# Logic.net
KiCad netlist of a schematic drawn in EAGLE
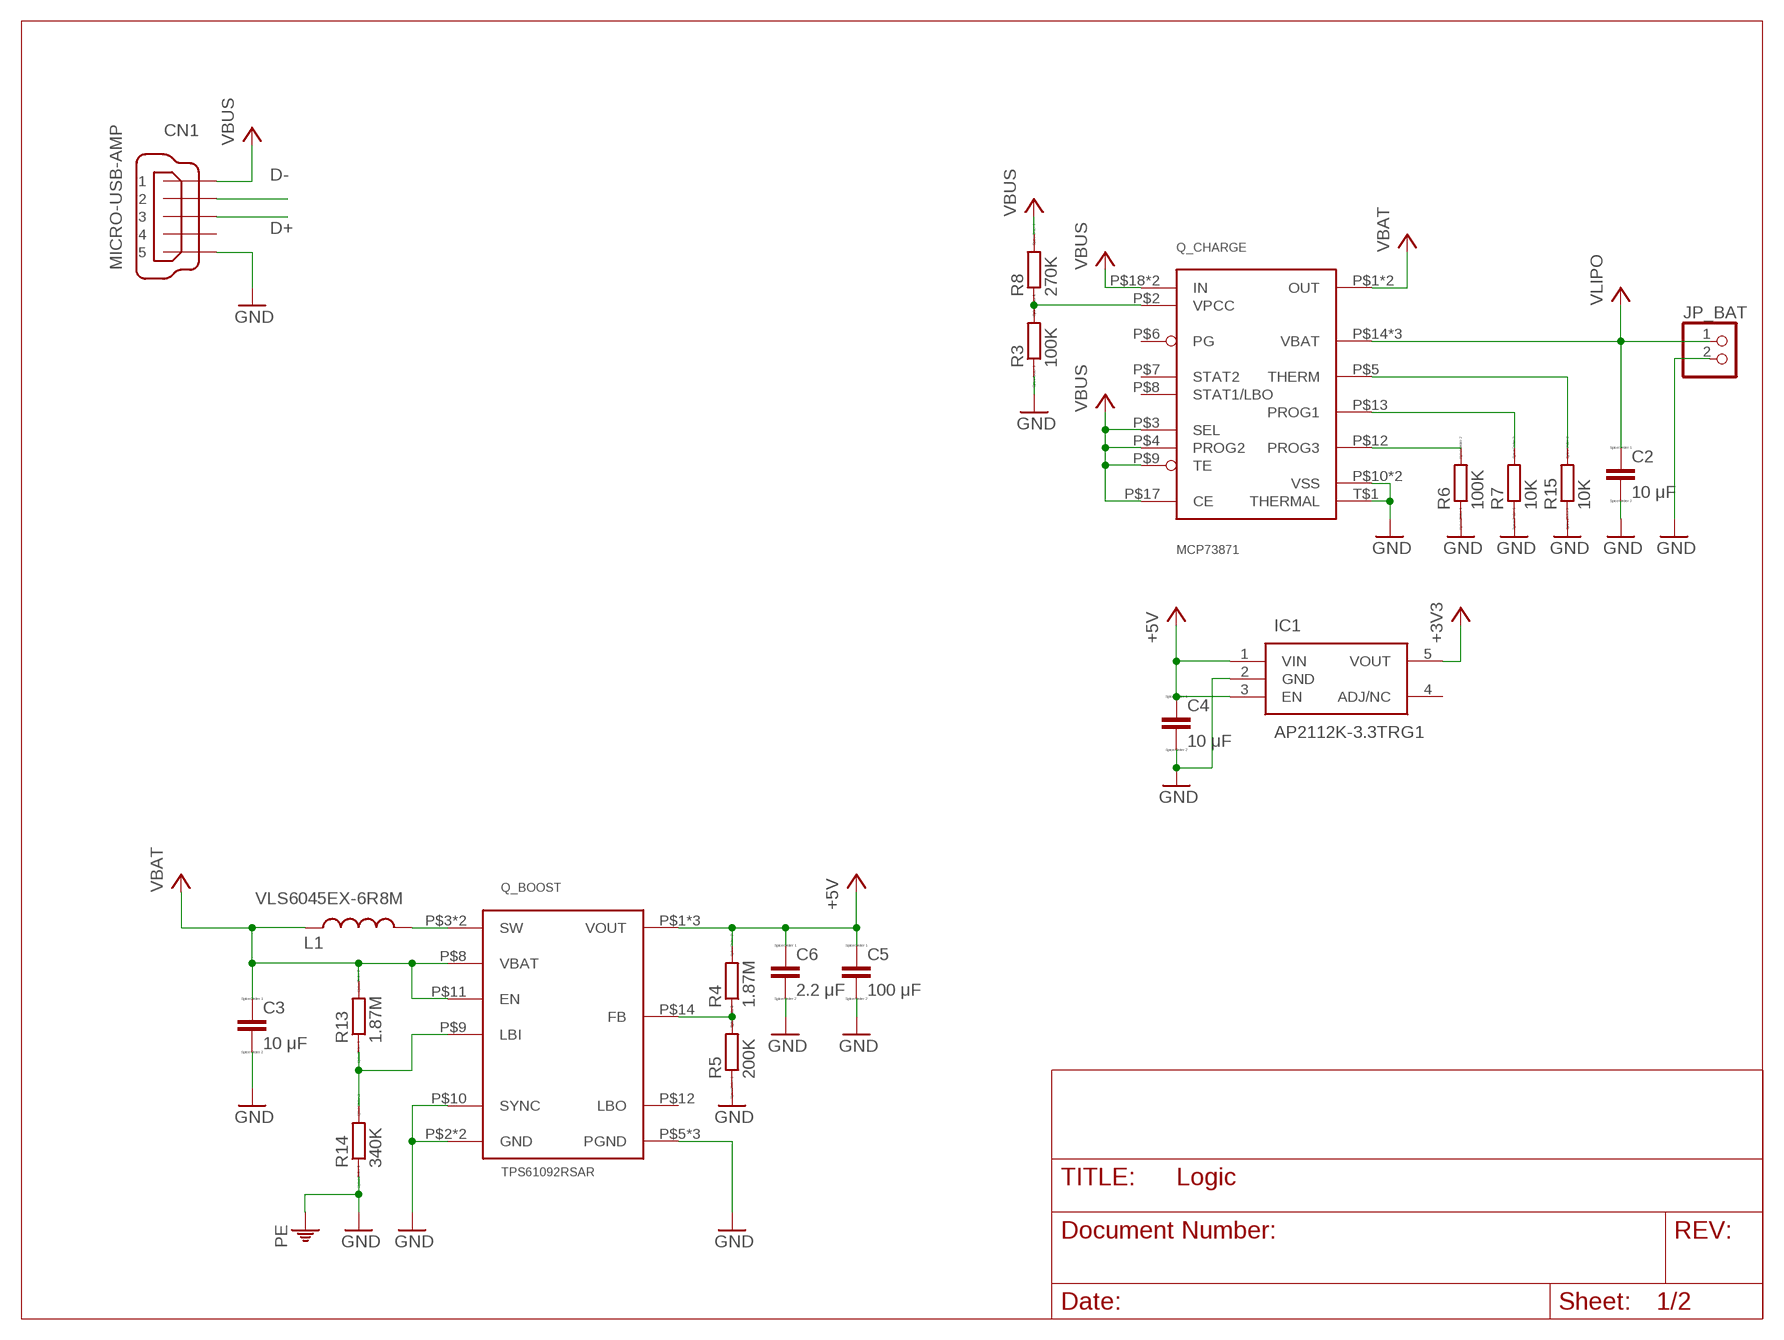
[diagram p0: schematic, sheet 1]
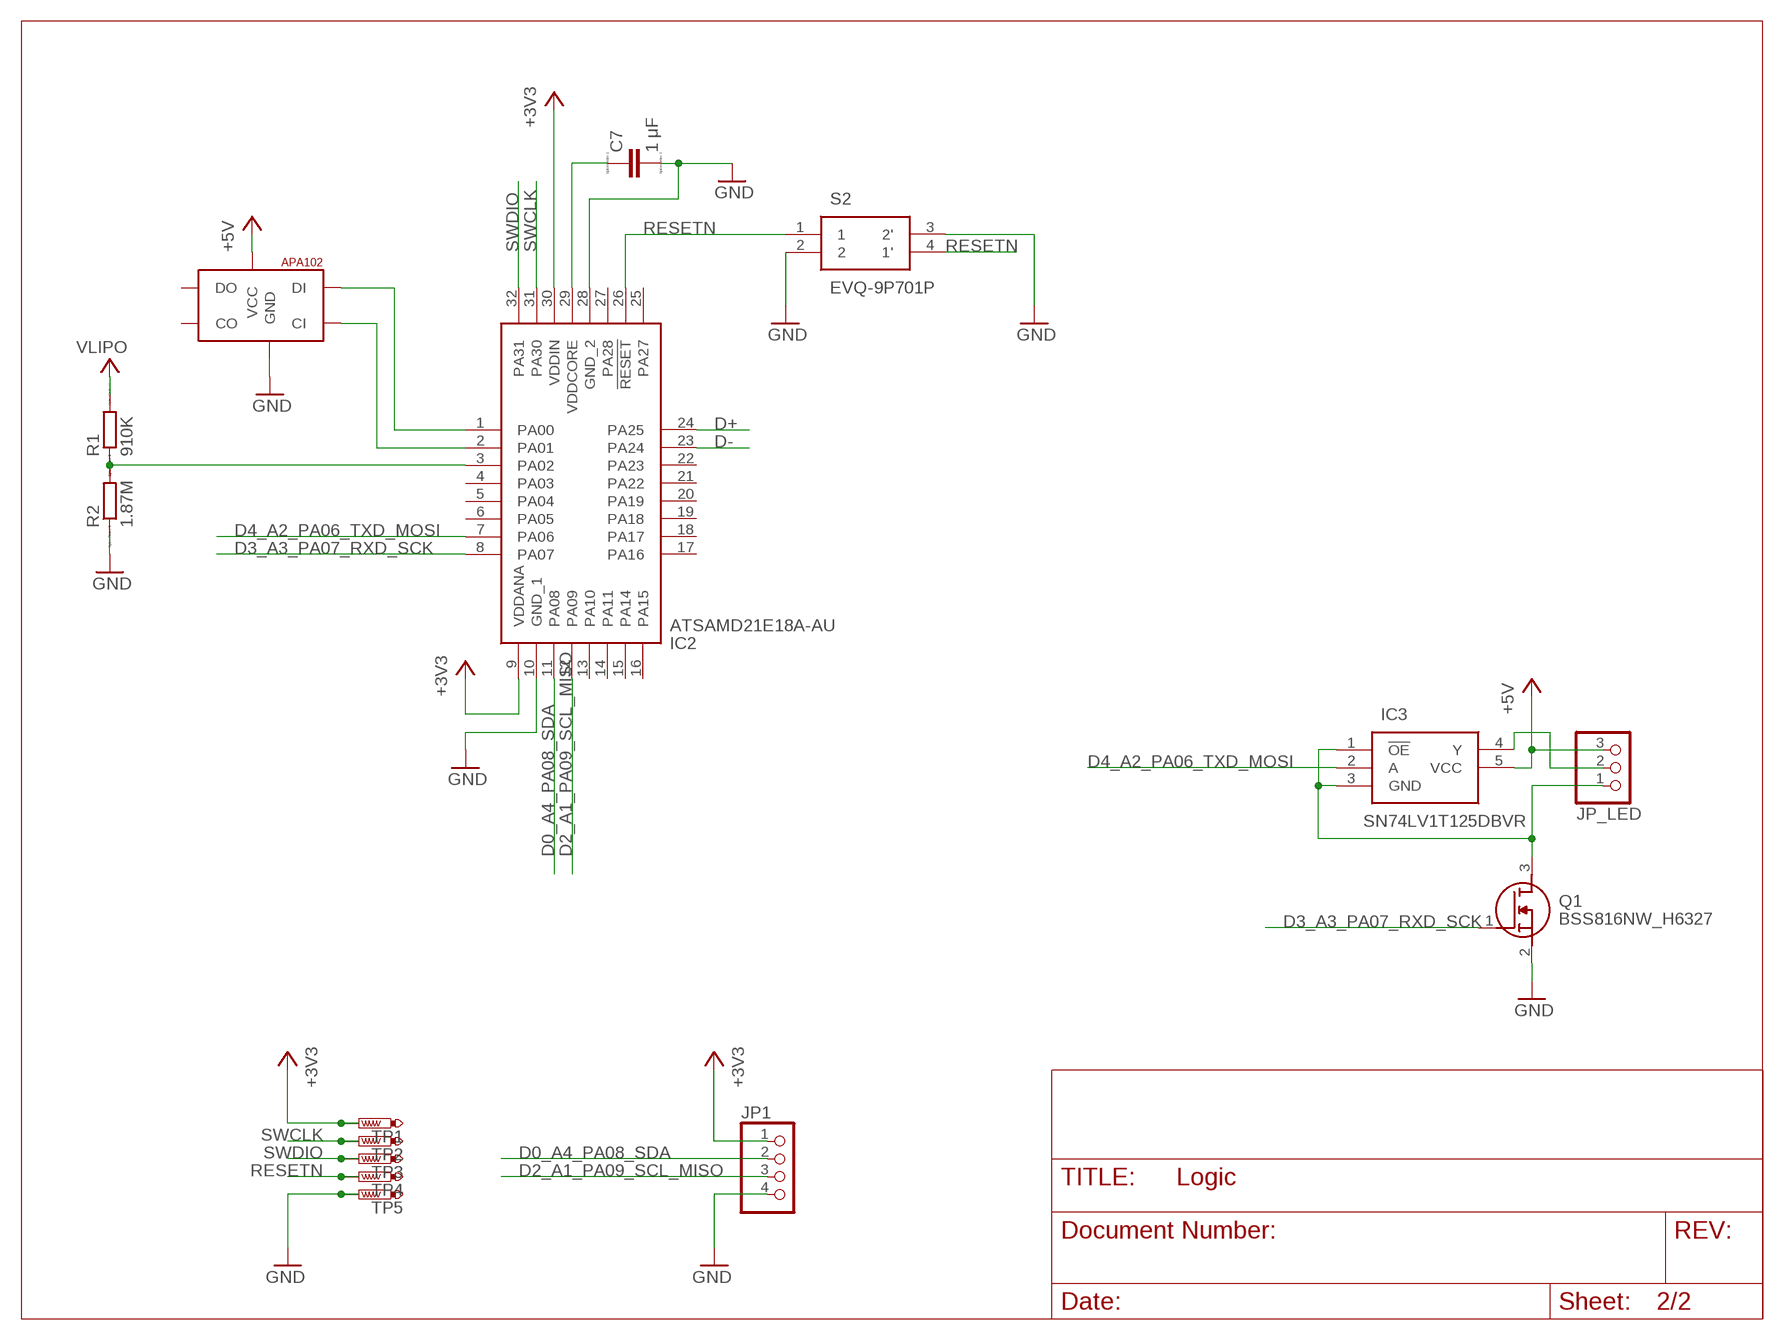
[diagram p1: schematic, sheet 2]

(export (version "E")
  (design (tool "Eeschema 10.0.6"))
  (components
    (comp (ref "C7")
      (value "1 μF")
      (footprint "eagle-import:C0603")
      (libsource (lib "eagle-import") (part "CC0603"))
    )
    (comp (ref "IC2")
      (value "ATSAMD21E18A-AU")
      (footprint "eagle-import:QFP80P900X900X120-32N")
      (fields (field (name "MOUSER_PART_NUMBER") "556-ATSAMD21E18A-AU"))
      (libsource (lib "eagle-import") (part "ATSAMD21E18A-AU"))
    )
    (comp (ref "IC3")
      (value "SN74LV1T125DBVR")
      (footprint "eagle-import:SOT95P280X145-5N")
      (fields (field (name "MOUSER_PART_NUMBER") "595-SN74LV1T125DBVR"))
      (libsource (lib "eagle-import") (part "SN74LV1T125DBVR"))
    )
    (comp (ref "JP1")
      (value "PINHD-1X4")
      (footprint "eagle-import:1X04")
      (libsource (lib "eagle-import") (part "PINHD-1X4"))
    )
    (comp (ref "JP_LED")
      (value "PINHD-1X3")
      (footprint "eagle-import:1X03")
      (libsource (lib "eagle-import") (part "PINHD-1X3"))
    )
    (comp (ref "Q1")
      (value "BSS816NW_H6327")
      (footprint "eagle-import:SOT65P210X100-3N")
      (fields
        (field (name "MANUFACTURER_PART_NUMBER") "BSS816NW H6327")
        (field (name "MOUSER_PART_NUMBER") "726-BSS816NWH6327")
      )
      (libsource (lib "eagle-import") (part "BSS816NW_H6327"))
    )
    (comp (ref "R1")
      (value "910K")
      (footprint "eagle-import:R0603")
      (libsource (lib "eagle-import") (part "RR0603"))
    )
    (comp (ref "R2")
      (value "1.87M")
      (footprint "eagle-import:R0603")
      (libsource (lib "eagle-import") (part "RR0603"))
    )
    (comp (ref "S2")
      (value "EVQ-9P701P")
      (footprint "eagle-import:EVQ-9P701P")
      (fields (field (name "MOUSER_PART_NUMBER") "667-EVQ-9P701P"))
      (libsource (lib "eagle-import") (part "EVQ-9P701P"))
    )
    (comp (ref "TP1")
      (value "PTR1B2,54")
      (footprint "eagle-import:B2,54")
      (libsource (lib "eagle-import") (part "PTR1B2,54"))
    )
    (comp (ref "TP2")
      (value "PTR1B2,54")
      (footprint "eagle-import:B2,54")
      (libsource (lib "eagle-import") (part "PTR1B2,54"))
    )
    (comp (ref "TP3")
      (value "PTR1B2,54")
      (footprint "eagle-import:B2,54")
      (libsource (lib "eagle-import") (part "PTR1B2,54"))
    )
    (comp (ref "TP4")
      (value "PTR1B2,54")
      (footprint "eagle-import:B2,54")
      (libsource (lib "eagle-import") (part "PTR1B2,54"))
    )
    (comp (ref "TP5")
      (value "PTR1B2,54")
      (footprint "eagle-import:B2,54")
      (libsource (lib "eagle-import") (part "PTR1B2,54"))
    )
    (comp (ref "U$2")
      (value "APA1025050")
      (footprint "eagle-import:APA102_5050")
      (libsource (lib "eagle-import") (part "APA1025050"))
    )
    (comp (ref "C2")
      (value "10 μF")
      (footprint "eagle-import:C0603")
      (libsource (lib "eagle-import") (part "CC0603"))
    )
    (comp (ref "C3")
      (value "10 μF")
      (footprint "eagle-import:C0603")
      (libsource (lib "eagle-import") (part "CC0603"))
    )
    (comp (ref "C4")
      (value "10 μF")
      (footprint "eagle-import:C0603")
      (libsource (lib "eagle-import") (part "CC0603"))
    )
    (comp (ref "C5")
      (value "100 μF")
      (footprint "eagle-import:C1206")
      (libsource (lib "eagle-import") (part "CC1206"))
    )
    (comp (ref "C6")
      (value "2.2 μF")
      (footprint "eagle-import:C0603")
      (libsource (lib "eagle-import") (part "CC0603"))
    )
    (comp (ref "CN1")
      (value "MICRO-USB-AMP")
      (footprint "eagle-import:10118193-0001LF")
      (libsource (lib "eagle-import") (part "MICRO-USB-AMP"))
    )
    (comp (ref "IC1")
      (value "AP2112K-3.3TRG1")
      (footprint "eagle-import:SOT95P282X130-5N")
      (fields (field (name "MOUSER_PART_NUMBER") "621-AP2112K-3.3TRG1"))
      (libsource (lib "eagle-import") (part "AP2112K-3.3TRG1"))
    )
    (comp (ref "JP_BAT")
      (value "PINHD-1X2")
      (footprint "eagle-import:1X02")
      (libsource (lib "eagle-import") (part "PINHD-1X2"))
    )
    (comp (ref "L1")
      (value "VLS6045EX-6R8M")
      (footprint "eagle-import:VLS6045EX-6R8M")
      (libsource (lib "eagle-import") (part "VLS6045EX-6R8M"))
    )
    (comp (ref "Q_BOOST")
      (value "TPS61092RSAR")
      (footprint "eagle-import:TPS61092RSAR")
      (libsource (lib "eagle-import") (part "TPS61092RSAR"))
    )
    (comp (ref "Q_CHARGE")
      (value "MCP73871")
      (footprint "eagle-import:MCP73871")
      (libsource (lib "eagle-import") (part "MCP73871"))
    )
    (comp (ref "R3")
      (value "100K")
      (footprint "eagle-import:R0603")
      (libsource (lib "eagle-import") (part "RR0603"))
    )
    (comp (ref "R4")
      (value "1.87M")
      (footprint "eagle-import:R0603")
      (libsource (lib "eagle-import") (part "RR0603"))
    )
    (comp (ref "R5")
      (value "200K")
      (footprint "eagle-import:R0603")
      (libsource (lib "eagle-import") (part "RR0603"))
    )
    (comp (ref "R6")
      (value "100K")
      (footprint "eagle-import:R0603")
      (libsource (lib "eagle-import") (part "RR0603"))
    )
    (comp (ref "R7")
      (value "10K")
      (footprint "eagle-import:R0603")
      (libsource (lib "eagle-import") (part "RR0603"))
    )
    (comp (ref "R8")
      (value "270K")
      (footprint "eagle-import:R0603")
      (libsource (lib "eagle-import") (part "RR0603"))
    )
    (comp (ref "R13")
      (value "1.87M")
      (footprint "eagle-import:R0603")
      (libsource (lib "eagle-import") (part "RR0603"))
    )
    (comp (ref "R14")
      (value "340K")
      (footprint "eagle-import:R0603")
      (libsource (lib "eagle-import") (part "RR0603"))
    )
    (comp (ref "R15")
      (value "10K")
      (footprint "eagle-import:R0603")
      (libsource (lib "eagle-import") (part "RR0603"))
    )
  )
  (nets
    (net (code "1") (name "+3V3") (class "Default")
      (node (ref "IC1") (pin "5") (pinfunction "VOUT_5") (pintype "bidirectional"))
      (node (ref "IC2") (pin "30") (pinfunction "VDDIN_30") (pintype "bidirectional"))
      (node (ref "IC2") (pin "9") (pinfunction "VDDANA_9") (pintype "bidirectional"))
      (node (ref "JP1") (pin "1") (pinfunction "1_1") (pintype "passive"))
      (node (ref "TP1") (pin "TP") (pinfunction "TP_TP") (pintype "input"))
    )
    (net (code "2") (name "+5V") (class "Default")
      (node (ref "C4") (pin "1") (pinfunction "1_1") (pintype "passive"))
      (node (ref "C5") (pin "1") (pinfunction "1_1") (pintype "passive"))
      (node (ref "C6") (pin "1") (pinfunction "1_1") (pintype "passive"))
      (node (ref "IC1") (pin "1") (pinfunction "VIN_1") (pintype "bidirectional"))
      (node (ref "IC1") (pin "3") (pinfunction "EN_3") (pintype "bidirectional"))
      (node (ref "IC3") (pin "5") (pinfunction "VCC_5") (pintype "bidirectional"))
      (node (ref "JP_LED") (pin "3") (pinfunction "3_3") (pintype "passive"))
      (node (ref "Q_BOOST") (pin "P$1") (pinfunction "VOUT_P$1") (pintype "bidirectional"))
      (node (ref "Q_BOOST") (pin "P$15") (pinfunction "VOUT_P$15") (pintype "bidirectional"))
      (node (ref "Q_BOOST") (pin "P$16") (pinfunction "VOUT_P$16") (pintype "bidirectional"))
      (node (ref "R4") (pin "2") (pinfunction "2_2") (pintype "passive"))
      (node (ref "U$2") (pin "1") (pinfunction "VCC_1") (pintype "bidirectional"))
    )
    (net (code "3") (name "D+") (class "Default")
      (node (ref "CN1") (pin "3") (pinfunction "3_3") (pintype "input"))
      (node (ref "IC2") (pin "24") (pinfunction "PA25_24") (pintype "bidirectional"))
    )
    (net (code "4") (name "D-") (class "Default")
      (node (ref "CN1") (pin "2") (pinfunction "2_2") (pintype "input"))
      (node (ref "IC2") (pin "23") (pinfunction "PA24_23") (pintype "bidirectional"))
    )
    (net (code "5") (name "D0_A4_PA08_SDA") (class "Default")
      (node (ref "IC2") (pin "11") (pinfunction "PA08_11") (pintype "bidirectional"))
      (node (ref "JP1") (pin "2") (pinfunction "2_2") (pintype "passive"))
    )
    (net (code "6") (name "D2_A1_PA09_SCL_MISO") (class "Default")
      (node (ref "IC2") (pin "12") (pinfunction "PA09_12") (pintype "bidirectional"))
      (node (ref "JP1") (pin "3") (pinfunction "3_3") (pintype "passive"))
    )
    (net (code "7") (name "D3_A3_PA07_RXD_SCK") (class "Default")
      (node (ref "IC2") (pin "8") (pinfunction "PA07_8") (pintype "bidirectional"))
      (node (ref "Q1") (pin "1") (pinfunction "G_1") (pintype "bidirectional"))
    )
    (net (code "8") (name "D4_A2_PA06_TXD_MOSI") (class "Default")
      (node (ref "IC2") (pin "7") (pinfunction "PA06_7") (pintype "bidirectional"))
      (node (ref "IC3") (pin "2") (pinfunction "A_2") (pintype "bidirectional"))
    )
    (net (code "9") (name "GND") (class "Default")
      (node (ref "C2") (pin "2") (pinfunction "2_2") (pintype "passive"))
      (node (ref "C3") (pin "2") (pinfunction "2_2") (pintype "passive"))
      (node (ref "C4") (pin "2") (pinfunction "2_2") (pintype "passive"))
      (node (ref "C5") (pin "2") (pinfunction "2_2") (pintype "passive"))
      (node (ref "C6") (pin "2") (pinfunction "2_2") (pintype "passive"))
      (node (ref "C7") (pin "2") (pinfunction "2_2") (pintype "passive"))
      (node (ref "CN1") (pin "5") (pinfunction "5_5") (pintype "input"))
      (node (ref "CN1") (pin "G1") (pinfunction "5_G1") (pintype "input"))
      (node (ref "CN1") (pin "G2") (pinfunction "5_G2") (pintype "input"))
      (node (ref "IC1") (pin "2") (pinfunction "GND_2") (pintype "bidirectional"))
      (node (ref "IC2") (pin "10") (pinfunction "GND_1_10") (pintype "bidirectional"))
      (node (ref "IC2") (pin "28") (pinfunction "GND_2_28") (pintype "bidirectional"))
      (node (ref "JP1") (pin "4") (pinfunction "4_4") (pintype "passive"))
      (node (ref "JP_BAT") (pin "2") (pinfunction "2_2") (pintype "passive"))
      (node (ref "Q1") (pin "2") (pinfunction "S_2") (pintype "bidirectional"))
      (node (ref "Q_BOOST") (pin "P$10") (pinfunction "SYNC_P$10") (pintype "bidirectional"))
      (node (ref "Q_BOOST") (pin "P$13") (pinfunction "GND_P$13") (pintype "bidirectional"))
      (node (ref "Q_BOOST") (pin "P$2") (pinfunction "GND_P$2") (pintype "bidirectional"))
      (node (ref "Q_BOOST") (pin "P$5") (pinfunction "PGND_P$5") (pintype "bidirectional"))
      (node (ref "Q_BOOST") (pin "P$6") (pinfunction "PGND_P$6") (pintype "bidirectional"))
      (node (ref "Q_BOOST") (pin "P$7") (pinfunction "PGND_P$7") (pintype "bidirectional"))
      (node (ref "Q_CHARGE") (pin "P$10") (pinfunction "VSS_P$10") (pintype "bidirectional"))
      (node (ref "Q_CHARGE") (pin "P$11") (pinfunction "VSS_P$11") (pintype "bidirectional"))
      (node (ref "Q_CHARGE") (pin "T$1") (pinfunction "THERMAL_T$1") (pintype "bidirectional"))
      (node (ref "R14") (pin "1") (pinfunction "1_1") (pintype "passive"))
      (node (ref "R15") (pin "1") (pinfunction "1_1") (pintype "passive"))
      (node (ref "R2") (pin "1") (pinfunction "1_1") (pintype "passive"))
      (node (ref "R3") (pin "1") (pinfunction "1_1") (pintype "passive"))
      (node (ref "R5") (pin "1") (pinfunction "1_1") (pintype "passive"))
      (node (ref "R6") (pin "1") (pinfunction "1_1") (pintype "passive"))
      (node (ref "R7") (pin "1") (pinfunction "1_1") (pintype "passive"))
      (node (ref "S2") (pin "2") (pinfunction "2_2") (pintype "bidirectional"))
      (node (ref "S2") (pin "3") (pinfunction "2'_3") (pintype "bidirectional"))
      (node (ref "TP5") (pin "TP") (pinfunction "TP_TP") (pintype "input"))
      (node (ref "U$2") (pin "6") (pinfunction "GND_6") (pintype "bidirectional"))
    )
    (net (code "10") (name "Net-(IC2-PA00)") (class "Default")
      (node (ref "IC2") (pin "1") (pinfunction "PA00_1") (pintype "bidirectional"))
      (node (ref "U$2") (pin "4") (pinfunction "DI_4") (pintype "bidirectional"))
    )
    (net (code "11") (name "Net-(IC2-PA01)") (class "Default")
      (node (ref "IC2") (pin "2") (pinfunction "PA01_2") (pintype "bidirectional"))
      (node (ref "U$2") (pin "5") (pinfunction "CI_5") (pintype "bidirectional"))
    )
    (net (code "12") (name "Net-(IC2-PA02)") (class "Default")
      (node (ref "IC2") (pin "3") (pinfunction "PA02_3") (pintype "bidirectional"))
      (node (ref "R1") (pin "1") (pinfunction "1_1") (pintype "passive"))
      (node (ref "R2") (pin "2") (pinfunction "2_2") (pintype "passive"))
    )
    (net (code "13") (name "Net-(IC2-VDDCORE)") (class "Default")
      (node (ref "C7") (pin "1") (pinfunction "1_1") (pintype "passive"))
      (node (ref "IC2") (pin "29") (pinfunction "VDDCORE_29") (pintype "bidirectional"))
    )
    (net (code "14") (name "Net-(IC3-GND)") (class "Default")
      (node (ref "IC3") (pin "1") (pinfunction "~{OE}_1") (pintype "bidirectional"))
      (node (ref "IC3") (pin "3") (pinfunction "GND_3") (pintype "bidirectional"))
      (node (ref "JP_LED") (pin "1") (pinfunction "1_1") (pintype "passive"))
      (node (ref "Q1") (pin "3") (pinfunction "D_3") (pintype "power_in"))
    )
    (net (code "15") (name "Net-(IC3-Y)") (class "Default")
      (node (ref "IC3") (pin "4") (pinfunction "Y_4") (pintype "bidirectional"))
      (node (ref "JP_LED") (pin "2") (pinfunction "2_2") (pintype "passive"))
    )
    (net (code "16") (name "Net-(L1-2)") (class "Default")
      (node (ref "L1") (pin "P$2") (pinfunction "2_P$2") (pintype "passive"))
      (node (ref "Q_BOOST") (pin "P$3") (pinfunction "SW_P$3") (pintype "bidirectional"))
      (node (ref "Q_BOOST") (pin "P$4") (pinfunction "SW_P$4") (pintype "bidirectional"))
    )
    (net (code "17") (name "Net-(Q_BOOST-FB)") (class "Default")
      (node (ref "Q_BOOST") (pin "P$14") (pinfunction "FB_P$14") (pintype "bidirectional"))
      (node (ref "R4") (pin "1") (pinfunction "1_1") (pintype "passive"))
      (node (ref "R5") (pin "2") (pinfunction "2_2") (pintype "passive"))
    )
    (net (code "18") (name "Net-(Q_BOOST-LBI)") (class "Default")
      (node (ref "Q_BOOST") (pin "P$9") (pinfunction "LBI_P$9") (pintype "bidirectional"))
      (node (ref "R13") (pin "1") (pinfunction "1_1") (pintype "passive"))
      (node (ref "R14") (pin "2") (pinfunction "2_2") (pintype "passive"))
    )
    (net (code "19") (name "Net-(Q_CHARGE-PROG1)") (class "Default")
      (node (ref "Q_CHARGE") (pin "P$13") (pinfunction "PROG1_P$13") (pintype "bidirectional"))
      (node (ref "R7") (pin "2") (pinfunction "2_2") (pintype "passive"))
    )
    (net (code "20") (name "Net-(Q_CHARGE-PROG3)") (class "Default")
      (node (ref "Q_CHARGE") (pin "P$12") (pinfunction "PROG3_P$12") (pintype "bidirectional"))
      (node (ref "R6") (pin "2") (pinfunction "2_2") (pintype "passive"))
    )
    (net (code "21") (name "Net-(Q_CHARGE-THERM)") (class "Default")
      (node (ref "Q_CHARGE") (pin "P$5") (pinfunction "THERM_P$5") (pintype "bidirectional"))
      (node (ref "R15") (pin "2") (pinfunction "2_2") (pintype "passive"))
    )
    (net (code "22") (name "Net-(Q_CHARGE-VPCC)") (class "Default")
      (node (ref "Q_CHARGE") (pin "P$2") (pinfunction "VPCC_P$2") (pintype "bidirectional"))
      (node (ref "R3") (pin "2") (pinfunction "2_2") (pintype "passive"))
      (node (ref "R8") (pin "1") (pinfunction "1_1") (pintype "passive"))
    )
    (net (code "23") (name "RESETN") (class "Default")
      (node (ref "IC2") (pin "26") (pinfunction "~{RESET}_26") (pintype "bidirectional"))
      (node (ref "S2") (pin "1") (pinfunction "1_1") (pintype "bidirectional"))
      (node (ref "S2") (pin "4") (pinfunction "1'_4") (pintype "bidirectional"))
      (node (ref "TP4") (pin "TP") (pinfunction "TP_TP") (pintype "input"))
    )
    (net (code "24") (name "SWCLK") (class "Default")
      (node (ref "IC2") (pin "31") (pinfunction "PA30_31") (pintype "bidirectional"))
      (node (ref "TP2") (pin "TP") (pinfunction "TP_TP") (pintype "input"))
    )
    (net (code "25") (name "SWDIO") (class "Default")
      (node (ref "IC2") (pin "32") (pinfunction "PA31_32") (pintype "bidirectional"))
      (node (ref "TP3") (pin "TP") (pinfunction "TP_TP") (pintype "input"))
    )
    (net (code "26") (name "VBAT") (class "Default")
      (node (ref "C3") (pin "1") (pinfunction "1_1") (pintype "passive"))
      (node (ref "L1") (pin "P$1") (pinfunction "1_P$1") (pintype "passive"))
      (node (ref "Q_BOOST") (pin "P$11") (pinfunction "EN_P$11") (pintype "bidirectional"))
      (node (ref "Q_BOOST") (pin "P$8") (pinfunction "VBAT_P$8") (pintype "bidirectional"))
      (node (ref "Q_CHARGE") (pin "P$1") (pinfunction "OUT_P$1") (pintype "bidirectional"))
      (node (ref "Q_CHARGE") (pin "P$20") (pinfunction "OUT_P$20") (pintype "bidirectional"))
      (node (ref "R13") (pin "2") (pinfunction "2_2") (pintype "passive"))
    )
    (net (code "27") (name "VBUS") (class "Default")
      (node (ref "CN1") (pin "1") (pinfunction "1_1") (pintype "input"))
      (node (ref "Q_CHARGE") (pin "P$17") (pinfunction "CE_P$17") (pintype "bidirectional"))
      (node (ref "Q_CHARGE") (pin "P$18") (pinfunction "IN_P$18") (pintype "bidirectional"))
      (node (ref "Q_CHARGE") (pin "P$19") (pinfunction "IN_P$19") (pintype "bidirectional"))
      (node (ref "Q_CHARGE") (pin "P$3") (pinfunction "SEL_P$3") (pintype "bidirectional"))
      (node (ref "Q_CHARGE") (pin "P$4") (pinfunction "PROG2_P$4") (pintype "bidirectional"))
      (node (ref "Q_CHARGE") (pin "P$9") (pinfunction "TE_P$9") (pintype "bidirectional"))
      (node (ref "R8") (pin "2") (pinfunction "2_2") (pintype "passive"))
    )
    (net (code "28") (name "VLIPO") (class "Default")
      (node (ref "C2") (pin "1") (pinfunction "1_1") (pintype "passive"))
      (node (ref "JP_BAT") (pin "1") (pinfunction "1_1") (pintype "passive"))
      (node (ref "Q_CHARGE") (pin "P$14") (pinfunction "VBAT_P$14") (pintype "bidirectional"))
      (node (ref "Q_CHARGE") (pin "P$15") (pinfunction "VBAT_P$15") (pintype "bidirectional"))
      (node (ref "Q_CHARGE") (pin "P$16") (pinfunction "VBAT_P$16") (pintype "bidirectional"))
      (node (ref "R1") (pin "2") (pinfunction "2_2") (pintype "passive"))
    )
    (net (code "29") (name "unconnected-(CN1-Pad4)") (class "Default")
      (node (ref "CN1") (pin "4") (pinfunction "4_4") (pintype "input"))
    )
    (net (code "30") (name "unconnected-(IC1-ADJ{slash}NC-Pad4)") (class "Default")
      (node (ref "IC1") (pin "4") (pinfunction "ADJ/NC_4") (pintype "bidirectional"))
    )
    (net (code "31") (name "unconnected-(IC2-PA03-Pad4)") (class "Default")
      (node (ref "IC2") (pin "4") (pinfunction "PA03_4") (pintype "bidirectional"))
    )
    (net (code "32") (name "unconnected-(IC2-PA04-Pad5)") (class "Default")
      (node (ref "IC2") (pin "5") (pinfunction "PA04_5") (pintype "bidirectional"))
    )
    (net (code "33") (name "unconnected-(IC2-PA05-Pad6)") (class "Default")
      (node (ref "IC2") (pin "6") (pinfunction "PA05_6") (pintype "bidirectional"))
    )
    (net (code "34") (name "unconnected-(IC2-PA10-Pad13)") (class "Default")
      (node (ref "IC2") (pin "13") (pinfunction "PA10_13") (pintype "bidirectional"))
    )
    (net (code "35") (name "unconnected-(IC2-PA11-Pad14)") (class "Default")
      (node (ref "IC2") (pin "14") (pinfunction "PA11_14") (pintype "bidirectional"))
    )
    (net (code "36") (name "unconnected-(IC2-PA14-Pad15)") (class "Default")
      (node (ref "IC2") (pin "15") (pinfunction "PA14_15") (pintype "bidirectional"))
    )
    (net (code "37") (name "unconnected-(IC2-PA15-Pad16)") (class "Default")
      (node (ref "IC2") (pin "16") (pinfunction "PA15_16") (pintype "bidirectional"))
    )
    (net (code "38") (name "unconnected-(IC2-PA16-Pad17)") (class "Default")
      (node (ref "IC2") (pin "17") (pinfunction "PA16_17") (pintype "bidirectional"))
    )
    (net (code "39") (name "unconnected-(IC2-PA17-Pad18)") (class "Default")
      (node (ref "IC2") (pin "18") (pinfunction "PA17_18") (pintype "bidirectional"))
    )
    (net (code "40") (name "unconnected-(IC2-PA18-Pad19)") (class "Default")
      (node (ref "IC2") (pin "19") (pinfunction "PA18_19") (pintype "bidirectional"))
    )
    (net (code "41") (name "unconnected-(IC2-PA19-Pad20)") (class "Default")
      (node (ref "IC2") (pin "20") (pinfunction "PA19_20") (pintype "bidirectional"))
    )
    (net (code "42") (name "unconnected-(IC2-PA22-Pad21)") (class "Default")
      (node (ref "IC2") (pin "21") (pinfunction "PA22_21") (pintype "bidirectional"))
    )
    (net (code "43") (name "unconnected-(IC2-PA23-Pad22)") (class "Default")
      (node (ref "IC2") (pin "22") (pinfunction "PA23_22") (pintype "bidirectional"))
    )
    (net (code "44") (name "unconnected-(IC2-PA27-Pad25)") (class "Default")
      (node (ref "IC2") (pin "25") (pinfunction "PA27_25") (pintype "bidirectional"))
    )
    (net (code "45") (name "unconnected-(IC2-PA28-Pad27)") (class "Default")
      (node (ref "IC2") (pin "27") (pinfunction "PA28_27") (pintype "bidirectional"))
    )
    (net (code "46") (name "unconnected-(Q_BOOST-LBO-PadP$12)") (class "Default")
      (node (ref "Q_BOOST") (pin "P$12") (pinfunction "LBO_P$12") (pintype "bidirectional"))
    )
    (net (code "47") (name "unconnected-(Q_CHARGE-PG-PadP$6)") (class "Default")
      (node (ref "Q_CHARGE") (pin "P$6") (pinfunction "PG_P$6") (pintype "bidirectional"))
    )
    (net (code "48") (name "unconnected-(Q_CHARGE-STAT1{slash}LBO-PadP$8)") (class "Default")
      (node (ref "Q_CHARGE") (pin "P$8") (pinfunction "STAT1/LBO_P$8") (pintype "bidirectional"))
    )
    (net (code "49") (name "unconnected-(Q_CHARGE-STAT2-PadP$7)") (class "Default")
      (node (ref "Q_CHARGE") (pin "P$7") (pinfunction "STAT2_P$7") (pintype "bidirectional"))
    )
    (net (code "50") (name "unconnected-(U$2-CO-Pad2)") (class "Default")
      (node (ref "U$2") (pin "2") (pinfunction "CO_2") (pintype "bidirectional"))
    )
    (net (code "51") (name "unconnected-(U$2-DO-Pad3)") (class "Default")
      (node (ref "U$2") (pin "3") (pinfunction "DO_3") (pintype "bidirectional"))
    )
  )
)
